# KC_BaseBoard4CompareTest-V0_2_NT_Pos_2.net
KiCad netlist of a schematic drawn in Altium Designer
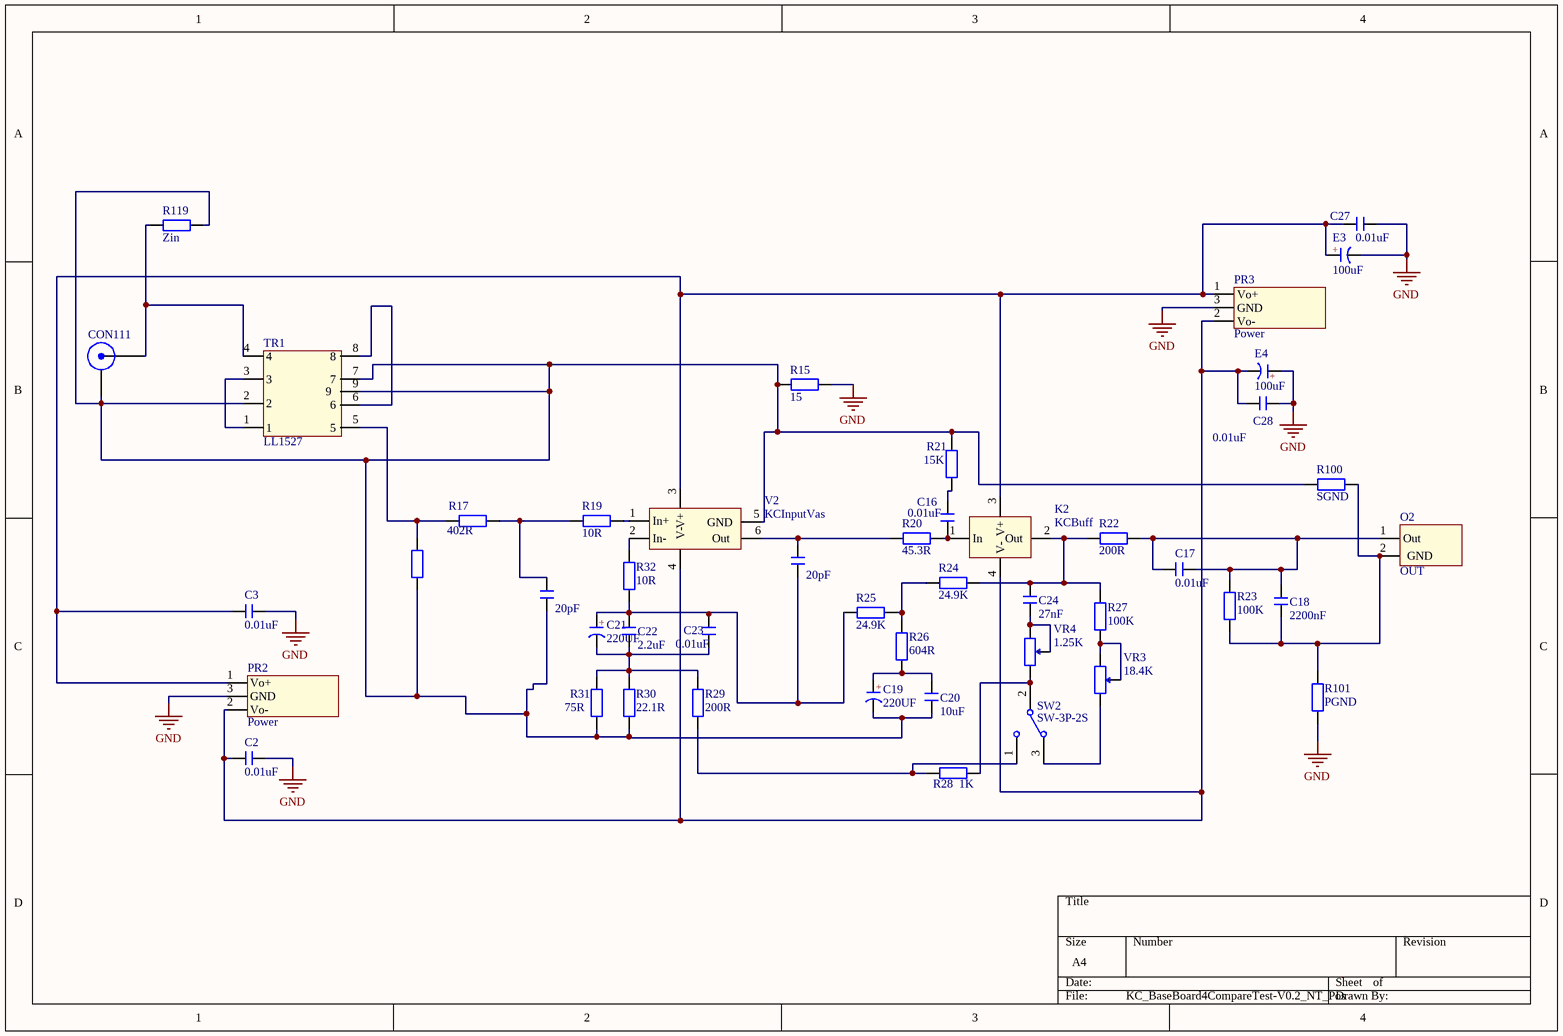
[diagram p0: KC_BaseBoard4CompareTest-V0.2_NT_Pos_2.SchDoc]

(export (version "E")
  (design (tool "Eeschema 10.0.6"))
  (components
    (comp (ref "C2")
      (value "0.01uF")
      (footprint "CBB 6.3*6.3*5")
      (description "CBB电容")
      (fields (field (name "版权归属") "源创客"))
      (libsource (lib "电阻-电容-电感") (part "C-CBB"))
    )
    (comp (ref "C3")
      (value "0.01uF")
      (footprint "CBB 6.3*6.3*5")
      (description "CBB电容")
      (fields (field (name "版权归属") "源创客"))
      (libsource (lib "电阻-电容-电感") (part "C-CBB"))
    )
    (comp (ref "C16")
      (value "0.01uF")
      (footprint "CBB 6.3*6.3*5")
      (description "CBB电容")
      (fields (field (name "版权归属") "源创客"))
      (libsource (lib "电阻-电容-电感") (part "C-CBB"))
    )
    (comp (ref "C17")
      (value "0.01uF")
      (footprint "CBB 6.3*6.3*5")
      (description "CBB电容")
      (fields (field (name "版权归属") "源创客"))
      (libsource (lib "电阻-电容-电感") (part "C-CBB"))
    )
    (comp (ref "C18")
      (value "2200nF")
      (footprint "CBB 6.3*6.3*5")
      (description "CBB电容")
      (fields (field (name "版权归属") "源创客"))
      (libsource (lib "电阻-电容-电感") (part "C-CBB"))
    )
    (comp (ref "C19")
      (value "220UF")
      (footprint "CAP 5.0*10*20")
      (description "直插电解电容")
      (fields (field (name "版权归属") "源创客"))
      (libsource (lib "") (part "C-CAP_1"))
    )
    (comp (ref "C20")
      (value "10uF")
      (footprint "CBB 6.3*6.3*5")
      (description "CBB电容")
      (fields (field (name "版权归属") "源创客"))
      (libsource (lib "电阻-电容-电感") (part "C-CBB"))
    )
    (comp (ref "C21")
      (value "220UF")
      (footprint "CAP 5.0*10*20")
      (description "直插电解电容")
      (fields (field (name "版权归属") "源创客"))
      (libsource (lib "") (part "C-CAP_1"))
    )
    (comp (ref "C22")
      (value "2.2uF")
      (footprint "CBB 6.3*6.3*5")
      (description "CBB电容")
      (fields (field (name "版权归属") "源创客"))
      (libsource (lib "电阻-电容-电感") (part "C-CBB"))
    )
    (comp (ref "C23")
      (value "0.01uF")
      (footprint "CBB 6.3*6.3*5")
      (description "CBB电容")
      (fields (field (name "版权归属") "源创客"))
      (libsource (lib "电阻-电容-电感") (part "C-CBB"))
    )
    (comp (ref "C24")
      (value "27nF")
      (footprint "CBB 6.3*6.3*5")
      (description "CBB电容")
      (fields (field (name "版权归属") "源创客"))
      (libsource (lib "电阻-电容-电感") (part "C-CBB"))
    )
    (comp (ref "C27")
      (value "0.01uF")
      (footprint "CBB 6.3*6.3*5")
      (description "CBB电容")
      (fields (field (name "版权归属") "源创客"))
      (libsource (lib "电阻-电容-电感") (part "C-CBB"))
    )
    (comp (ref "C28")
      (value "0.01uF")
      (footprint "CBB 6.3*6.3*5")
      (description "CBB电容")
      (fields (field (name "版权归属") "源创客"))
      (libsource (lib "电阻-电容-电感") (part "C-CBB"))
    )
    (comp (ref "C303")
      (value "20pF")
      (footprint "CBB 6.3*6.3*5")
      (description "CBB电容")
      (fields (field (name "版权归属") "源创客"))
      (libsource (lib "电阻-电容-电感") (part "C-CBB"))
    )
    (comp (ref "C403")
      (value "20pF")
      (footprint "CBB 6.3*6.3*5")
      (description "CBB电容")
      (fields (field (name "版权归属") "源创客"))
      (libsource (lib "电阻-电容-电感") (part "C-CBB"))
    )
    (comp (ref "CON111")
      (value "RCA")
      (footprint "RCA-RJ255")
      (description "RCA Connector")
      (fields (field (name "PUBLISHER") "Altium Limited"))
      (libsource (lib "Connectors") (part "RCA"))
    )
    (comp (ref "E3")
      (value "100uF")
      (footprint "CAP 5.0*6.5*12.5")
      (description "直插电解电容")
      (fields (field (name "版权归属") "源创客"))
      (libsource (lib "电阻-电容-电感") (part "C-CAP"))
    )
    (comp (ref "E4")
      (value "100uF")
      (footprint "CAP 5.0*6.5*12.5")
      (description "直插电解电容")
      (fields (field (name "版权归属") "源创客"))
      (libsource (lib "电阻-电容-电感") (part "C-CAP"))
    )
    (comp (ref "K2")
      (value "KCBuff")
      (footprint "KCBuff_M4")
      (description "King Cello Buffer Stage")
      (libsource (lib "KC_amp") (part "KCBuff"))
    )
    (comp (ref "O2")
      (value "OUT")
      (footprint "Signal_Terminal")
      (description "Signal Out")
      (libsource (lib "KC_amp") (part "Signal_Out"))
    )
    (comp (ref "PR2")
      (value "Power")
      (footprint "KC_MBPowerReg4Compare-1.5mm")
      (description "King Cello Compare Test Power")
      (libsource (lib "KC_amp") (part "MainBoardPowerRegulator4CompareTest"))
    )
    (comp (ref "PR3")
      (value "Power")
      (footprint "KC_MBPowerReg4Compare-1.5mm")
      (description "King Cello Compare Test Power")
      (libsource (lib "KC_amp") (part "MainBoardPowerRegulator4CompareTest"))
    )
    (comp (ref "R15")
      (value "15")
      (footprint "RS 1/4W")
      (description "直插色环电阻")
      (fields (field (name "版权归属") "源创客"))
      (libsource (lib "电阻-电容-电感") (part "R-CRR"))
    )
    (comp (ref "R17")
      (value "402R")
      (footprint "RS 1/4W")
      (description "直插色环电阻")
      (fields (field (name "版权归属") "源创客"))
      (libsource (lib "电阻-电容-电感") (part "R-CRR"))
    )
    (comp (ref "R19")
      (value "10R")
      (footprint "RS 1/4W")
      (description "直插色环电阻")
      (fields (field (name "版权归属") "源创客"))
      (libsource (lib "电阻-电容-电感") (part "R-CRR"))
    )
    (comp (ref "R20")
      (value "45.3R")
      (footprint "RS 1/4W")
      (description "直插色环电阻")
      (fields (field (name "版权归属") "源创客"))
      (libsource (lib "电阻-电容-电感") (part "R-CRR"))
    )
    (comp (ref "R21")
      (value "15K")
      (footprint "RS 1/4W")
      (description "直插色环电阻")
      (fields (field (name "版权归属") "源创客"))
      (libsource (lib "电阻-电容-电感") (part "R-CRR"))
    )
    (comp (ref "R22")
      (value "200R")
      (footprint "RS 1/4W")
      (description "直插色环电阻")
      (fields (field (name "版权归属") "源创客"))
      (libsource (lib "电阻-电容-电感") (part "R-CRR"))
    )
    (comp (ref "R23")
      (value "100K")
      (footprint "RS 1/4W")
      (description "直插色环电阻")
      (fields (field (name "版权归属") "源创客"))
      (libsource (lib "电阻-电容-电感") (part "R-CRR"))
    )
    (comp (ref "R24")
      (value "24.9K")
      (footprint "RS 1/4W")
      (description "直插色环电阻")
      (fields (field (name "版权归属") "源创客"))
      (libsource (lib "电阻-电容-电感") (part "R-CRR"))
    )
    (comp (ref "R25")
      (value "24.9K")
      (footprint "RS 1/4W")
      (description "直插色环电阻")
      (fields (field (name "版权归属") "源创客"))
      (libsource (lib "电阻-电容-电感") (part "R-CRR"))
    )
    (comp (ref "R26")
      (value "604R")
      (footprint "RS 1/4W")
      (description "直插色环电阻")
      (fields (field (name "版权归属") "源创客"))
      (libsource (lib "电阻-电容-电感") (part "R-CRR"))
    )
    (comp (ref "R27")
      (value "100K")
      (footprint "RS 1/4W")
      (description "直插色环电阻")
      (fields (field (name "版权归属") "源创客"))
      (libsource (lib "电阻-电容-电感") (part "R-CRR"))
    )
    (comp (ref "R28")
      (value "1K")
      (footprint "RS 1/4W")
      (description "直插色环电阻")
      (fields (field (name "版权归属") "源创客"))
      (libsource (lib "电阻-电容-电感") (part "R-CRR"))
    )
    (comp (ref "R29")
      (value "200R")
      (footprint "RS 1/4W")
      (description "直插色环电阻")
      (fields (field (name "版权归属") "源创客"))
      (libsource (lib "电阻-电容-电感") (part "R-CRR"))
    )
    (comp (ref "R30")
      (value "22.1R")
      (footprint "RS 1/4W")
      (description "直插色环电阻")
      (fields (field (name "版权归属") "源创客"))
      (libsource (lib "电阻-电容-电感") (part "R-CRR"))
    )
    (comp (ref "R31")
      (value "75R")
      (footprint "RS 1/4W")
      (description "直插色环电阻")
      (fields (field (name "版权归属") "源创客"))
      (libsource (lib "电阻-电容-电感") (part "R-CRR"))
    )
    (comp (ref "R32")
      (value "10R")
      (footprint "RS 1/4W")
      (description "直插色环电阻")
      (fields (field (name "版权归属") "源创客"))
      (libsource (lib "电阻-电容-电感") (part "R-CRR"))
    )
    (comp (ref "R100")
      (value "SGND")
      (footprint "RS 1/4W")
      (description "直插色环电阻")
      (fields (field (name "版权归属") "源创客"))
      (libsource (lib "电阻-电容-电感") (part "R-CRR"))
    )
    (comp (ref "R101")
      (value "PGND")
      (footprint "RS 1/4W")
      (description "直插色环电阻")
      (fields (field (name "版权归属") "源创客"))
      (libsource (lib "电阻-电容-电感") (part "R-CRR"))
    )
    (comp (ref "R119")
      (value "Zin")
      (footprint "RS 1/4W")
      (description "直插色环电阻")
      (fields (field (name "版权归属") "源创客"))
      (libsource (lib "电阻-电容-电感") (part "R-CRR"))
    )
    (comp (ref "R183")
      (value "47K")
      (footprint "RS 1/4W")
      (description "直插色环电阻")
      (fields (field (name "版权归属") "源创客"))
      (libsource (lib "电阻-电容-电感") (part "R-CRR"))
    )
    (comp (ref "SW2")
      (value "SW-3P-2S")
      (footprint "SS-12D06")
      (description "3 Pin 2 Switch")
      (libsource (lib "Connectors") (part "SW-3P-2S"))
    )
    (comp (ref "TR1")
      (value "LL1527")
      (footprint "LL1527")
      (description "Lundahl LL1527")
      (libsource (lib "KC_amp") (part "LL1527"))
    )
    (comp (ref "V2")
      (value "KCInputVas")
      (footprint "KCIn_VAS_M4")
      (description "King Cello Input Stage and VAS")
      (libsource (lib "KC_amp") (part "KCInputVas"))
    )
    (comp (ref "VR3")
      (value "18.4K")
      (footprint "RS 1/2W-VR")
      (description "直插可调电阻-顶调")
      (libsource (lib "电阻-电容-电感") (part "VR-W"))
    )
    (comp (ref "VR4")
      (value "1.25K")
      (footprint "RS 1/2W-VR")
      (description "直插可调电阻-顶调")
      (libsource (lib "电阻-电容-电感") (part "VR-W"))
    )
  )
  (nets
    (net (code "1") (name "GND") (class "Default")
      (node (ref "C2") (pin "2") (pinfunction "2_2") (pintype "passive"))
      (node (ref "C27") (pin "2") (pinfunction "2_2") (pintype "passive"))
      (node (ref "C28") (pin "2") (pinfunction "2_2") (pintype "passive"))
      (node (ref "C3") (pin "2") (pinfunction "2_2") (pintype "passive"))
      (node (ref "E3") (pin "2") (pinfunction "K_2") (pintype "passive"))
      (node (ref "E4") (pin "1") (pinfunction "A_1") (pintype "passive"))
      (node (ref "PR2") (pin "3") (pinfunction "GND_3") (pintype "passive"))
      (node (ref "PR3") (pin "3") (pinfunction "GND_3") (pintype "passive"))
      (node (ref "R101") (pin "1") (pinfunction "1_1") (pintype "passive"))
      (node (ref "R15") (pin "2") (pinfunction "2_2") (pintype "passive"))
    )
    (net (code "2") (name "Net-(C16-Pad2)") (class "Default")
      (node (ref "C16") (pin "2") (pinfunction "2_2") (pintype "passive"))
      (node (ref "R21") (pin "1") (pinfunction "1_1") (pintype "passive"))
    )
    (net (code "3") (name "Net-(C19-A)") (class "Default")
      (node (ref "C19") (pin "1") (pinfunction "A_1") (pintype "passive"))
      (node (ref "C20") (pin "1") (pinfunction "1_1") (pintype "passive"))
      (node (ref "R26") (pin "1") (pinfunction "1_1") (pintype "passive"))
    )
    (net (code "4") (name "Net-(C19-K)") (class "Default")
      (node (ref "C19") (pin "2") (pinfunction "K_2") (pintype "passive"))
      (node (ref "C20") (pin "2") (pinfunction "2_2") (pintype "passive"))
      (node (ref "C303") (pin "1") (pinfunction "1_1") (pintype "passive"))
      (node (ref "CON111") (pin "2") (pinfunction "Y_2") (pintype "passive"))
      (node (ref "R100") (pin "1") (pinfunction "1_1") (pintype "passive"))
      (node (ref "R119") (pin "2") (pinfunction "2_2") (pintype "passive"))
      (node (ref "R15") (pin "1") (pinfunction "1_1") (pintype "passive"))
      (node (ref "R183") (pin "1") (pinfunction "1_1") (pintype "passive"))
      (node (ref "R21") (pin "2") (pinfunction "2_2") (pintype "passive"))
      (node (ref "R30") (pin "1") (pinfunction "1_1") (pintype "passive"))
      (node (ref "R31") (pin "1") (pinfunction "1_1") (pintype "passive"))
      (node (ref "TR1") (pin "2") (pinfunction "2_2") (pintype "passive"))
      (node (ref "TR1") (pin "7") (pinfunction "7_7") (pintype "passive"))
      (node (ref "TR1") (pin "9") (pinfunction "9_9") (pintype "passive"))
      (node (ref "V2") (pin "5") (pinfunction "GND_5") (pintype "passive"))
    )
    (net (code "5") (name "Net-(C21-A)") (class "Default")
      (node (ref "C21") (pin "1") (pinfunction "A_1") (pintype "passive"))
      (node (ref "C22") (pin "1") (pinfunction "1_1") (pintype "passive"))
      (node (ref "C23") (pin "1") (pinfunction "1_1") (pintype "passive"))
      (node (ref "C403") (pin "1") (pinfunction "1_1") (pintype "passive"))
      (node (ref "R25") (pin "1") (pinfunction "1_1") (pintype "passive"))
      (node (ref "R32") (pin "1") (pinfunction "1_1") (pintype "passive"))
    )
    (net (code "6") (name "Net-(C21-K)") (class "Default")
      (node (ref "C21") (pin "2") (pinfunction "K_2") (pintype "passive"))
      (node (ref "C22") (pin "2") (pinfunction "2_2") (pintype "passive"))
      (node (ref "C23") (pin "2") (pinfunction "2_2") (pintype "passive"))
      (node (ref "R29") (pin "2") (pinfunction "2_2") (pintype "passive"))
      (node (ref "R30") (pin "2") (pinfunction "2_2") (pintype "passive"))
      (node (ref "R31") (pin "2") (pinfunction "2_2") (pintype "passive"))
    )
    (net (code "7") (name "Net-(C24-Pad2)") (class "Default")
      (node (ref "C24") (pin "2") (pinfunction "2_2") (pintype "passive"))
      (node (ref "VR4") (pin "1") (pinfunction "1_1") (pintype "passive"))
      (node (ref "VR4") (pin "3") (pinfunction "3_3") (pintype "passive"))
    )
    (net (code "8") (name "Net-(C303-Pad2)") (class "Default")
      (node (ref "C303") (pin "2") (pinfunction "2_2") (pintype "passive"))
      (node (ref "R17") (pin "2") (pinfunction "2_2") (pintype "passive"))
      (node (ref "R19") (pin "1") (pinfunction "1_1") (pintype "passive"))
    )
    (net (code "9") (name "Net-(CON111-X)") (class "Default")
      (node (ref "CON111") (pin "1") (pinfunction "X_1") (pintype "passive"))
      (node (ref "R119") (pin "1") (pinfunction "1_1") (pintype "passive"))
      (node (ref "TR1") (pin "4") (pinfunction "4_4") (pintype "passive"))
    )
    (net (code "10") (name "Net-(E3-A)") (class "Default")
      (node (ref "C27") (pin "1") (pinfunction "1_1") (pintype "passive"))
      (node (ref "C3") (pin "1") (pinfunction "1_1") (pintype "passive"))
      (node (ref "E3") (pin "1") (pinfunction "A_1") (pintype "passive"))
      (node (ref "K2") (pin "3") (pinfunction "V+_3") (pintype "passive"))
      (node (ref "PR2") (pin "1") (pinfunction "Vo+_1") (pintype "passive"))
      (node (ref "PR3") (pin "1") (pinfunction "Vo+_1") (pintype "passive"))
      (node (ref "V2") (pin "3") (pinfunction "V+_3") (pintype "passive"))
    )
    (net (code "11") (name "Net-(E4-K)") (class "Default")
      (node (ref "C2") (pin "1") (pinfunction "1_1") (pintype "passive"))
      (node (ref "C28") (pin "1") (pinfunction "1_1") (pintype "passive"))
      (node (ref "E4") (pin "2") (pinfunction "K_2") (pintype "passive"))
      (node (ref "K2") (pin "4") (pinfunction "V-_4") (pintype "passive"))
      (node (ref "PR2") (pin "2") (pinfunction "Vo-_2") (pintype "passive"))
      (node (ref "PR3") (pin "2") (pinfunction "Vo-_2") (pintype "passive"))
      (node (ref "V2") (pin "4") (pinfunction "V-_4") (pintype "passive"))
    )
    (net (code "12") (name "Net-(K2-In)") (class "Default")
      (node (ref "C16") (pin "1") (pinfunction "1_1") (pintype "passive"))
      (node (ref "K2") (pin "1") (pinfunction "In_1") (pintype "passive"))
      (node (ref "R20") (pin "2") (pinfunction "2_2") (pintype "passive"))
    )
    (net (code "13") (name "Net-(K2-Out)") (class "Default")
      (node (ref "C24") (pin "1") (pinfunction "1_1") (pintype "passive"))
      (node (ref "K2") (pin "2") (pinfunction "Out_2") (pintype "passive"))
      (node (ref "R22") (pin "2") (pinfunction "2_2") (pintype "passive"))
      (node (ref "R24") (pin "2") (pinfunction "2_2") (pintype "passive"))
      (node (ref "R27") (pin "1") (pinfunction "1_1") (pintype "passive"))
    )
    (net (code "14") (name "Net-(O2-GND)") (class "Default")
      (node (ref "C18") (pin "2") (pinfunction "2_2") (pintype "passive"))
      (node (ref "O2") (pin "2") (pinfunction "GND_2") (pintype "passive"))
      (node (ref "R100") (pin "2") (pinfunction "2_2") (pintype "passive"))
      (node (ref "R101") (pin "2") (pinfunction "2_2") (pintype "passive"))
      (node (ref "R23") (pin "2") (pinfunction "2_2") (pintype "passive"))
    )
    (net (code "15") (name "Net-(O2-Out)") (class "Default")
      (node (ref "C17") (pin "1") (pinfunction "1_1") (pintype "passive"))
      (node (ref "C17") (pin "2") (pinfunction "2_2") (pintype "passive"))
      (node (ref "C18") (pin "1") (pinfunction "1_1") (pintype "passive"))
      (node (ref "O2") (pin "1") (pinfunction "Out_1") (pintype "passive"))
      (node (ref "R22") (pin "1") (pinfunction "1_1") (pintype "passive"))
      (node (ref "R23") (pin "1") (pinfunction "1_1") (pintype "passive"))
    )
    (net (code "16") (name "Net-(R17-Pad1)") (class "Default")
      (node (ref "R17") (pin "1") (pinfunction "1_1") (pintype "passive"))
      (node (ref "R183") (pin "2") (pinfunction "2_2") (pintype "passive"))
      (node (ref "TR1") (pin "5") (pinfunction "5_5") (pintype "passive"))
    )
    (net (code "17") (name "Net-(R24-Pad1)") (class "Default")
      (node (ref "R24") (pin "1") (pinfunction "1_1") (pintype "passive"))
      (node (ref "R25") (pin "2") (pinfunction "2_2") (pintype "passive"))
      (node (ref "R26") (pin "2") (pinfunction "2_2") (pintype "passive"))
    )
    (net (code "18") (name "Net-(R27-Pad2)") (class "Default")
      (node (ref "R27") (pin "2") (pinfunction "2_2") (pintype "passive"))
      (node (ref "VR3") (pin "1") (pinfunction "1_1") (pintype "passive"))
      (node (ref "VR3") (pin "3") (pinfunction "3_3") (pintype "passive"))
    )
    (net (code "19") (name "Net-(R28-Pad1)") (class "Default")
      (node (ref "R28") (pin "1") (pinfunction "1_1") (pintype "passive"))
      (node (ref "R29") (pin "1") (pinfunction "1_1") (pintype "passive"))
      (node (ref "SW2") (pin "1") (pinfunction "1_1") (pintype "passive"))
    )
    (net (code "20") (name "Net-(R28-Pad2)") (class "Default")
      (node (ref "R28") (pin "2") (pinfunction "2_2") (pintype "passive"))
      (node (ref "SW2") (pin "2") (pinfunction "2_2") (pintype "passive"))
      (node (ref "VR4") (pin "2") (pinfunction "2_2") (pintype "passive"))
    )
    (net (code "21") (name "Net-(SW2-Pad3)") (class "Default")
      (node (ref "SW2") (pin "3") (pinfunction "3_3") (pintype "passive"))
      (node (ref "VR3") (pin "2") (pinfunction "2_2") (pintype "passive"))
    )
    (net (code "22") (name "Net-(TR1-Pad1)") (class "Default")
      (node (ref "TR1") (pin "1") (pinfunction "1_1") (pintype "passive"))
      (node (ref "TR1") (pin "3") (pinfunction "3_3") (pintype "passive"))
    )
    (net (code "23") (name "Net-(TR1-Pad6)") (class "Default")
      (node (ref "TR1") (pin "6") (pinfunction "6_6") (pintype "passive"))
      (node (ref "TR1") (pin "8") (pinfunction "8_8") (pintype "passive"))
    )
    (net (code "24") (name "Net-(V2-In+)") (class "Default")
      (node (ref "R19") (pin "2") (pinfunction "2_2") (pintype "passive"))
      (node (ref "V2") (pin "1") (pinfunction "In+_1") (pintype "passive"))
    )
    (net (code "25") (name "Net-(V2-In-)") (class "Default")
      (node (ref "R32") (pin "2") (pinfunction "2_2") (pintype "passive"))
      (node (ref "V2") (pin "2") (pinfunction "In-_2") (pintype "passive"))
    )
    (net (code "26") (name "Net-(V2-Out)") (class "Default")
      (node (ref "C403") (pin "2") (pinfunction "2_2") (pintype "passive"))
      (node (ref "R20") (pin "1") (pinfunction "1_1") (pintype "passive"))
      (node (ref "V2") (pin "6") (pinfunction "Out_6") (pintype "passive"))
    )
  )
)
